# P2345.net
KiCad netlist of a schematic drawn in EAGLE
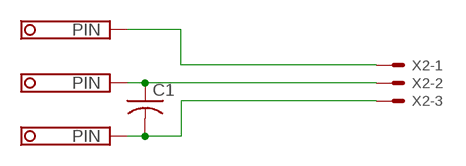
[diagram p0: schematic, sheet 1]

(export (version "E")
  (design (tool "Eeschema 10.0.6"))
  (components
    (comp (ref "C1")
      (value "C-US050-024X044")
      (footprint "eagle-import:C050-024X044")
      (libsource (lib "eagle-import") (part "C-US050-024X044"))
    )
    (comp (ref "X1")
      (value "TERMINAL-BLOCK-3.5MM-3-PIN-ROUND-PAD")
      (footprint "eagle-import:TERMINAL-BLOCK-3-PIN-3.5MM-ROUND-PAD")
      (libsource (lib "eagle-import") (part "TERMINAL-BLOCK-3.5MM-3-PIN-ROUND-PAD"))
    )
    (comp (ref "X2")
      (value "JST-XH-03-PIN-ROUND-PAD")
      (footprint "eagle-import:JST-XH-03-PACKAGE-ROUND-PAD")
      (libsource (lib "eagle-import") (part "JST-XH-03-PIN-ROUND-PAD"))
    )
  )
  (nets
    (net (code "1") (name "Net-(X1A-VCC)") (class "Default")
      (node (ref "X1") (pin "1") (pinfunction "VCC_1") (pintype "passive"))
      (node (ref "X2") (pin "1") (pinfunction "S_1") (pintype "passive"))
    )
    (net (code "2") (name "Net-(X1B-VCC)") (class "Default")
      (node (ref "C1") (pin "1") (pinfunction "1_1") (pintype "passive"))
      (node (ref "X1") (pin "2") (pinfunction "VCC_2") (pintype "passive"))
      (node (ref "X2") (pin "2") (pinfunction "S_2") (pintype "passive"))
    )
    (net (code "3") (name "Net-(X1C-VCC)") (class "Default")
      (node (ref "C1") (pin "2") (pinfunction "2_2") (pintype "passive"))
      (node (ref "X1") (pin "3") (pinfunction "VCC_3") (pintype "passive"))
      (node (ref "X2") (pin "3") (pinfunction "S_3") (pintype "passive"))
    )
  )
)
